# MRF24J40MA_Breakout_verA.net
KiCad netlist of a schematic drawn in EAGLE
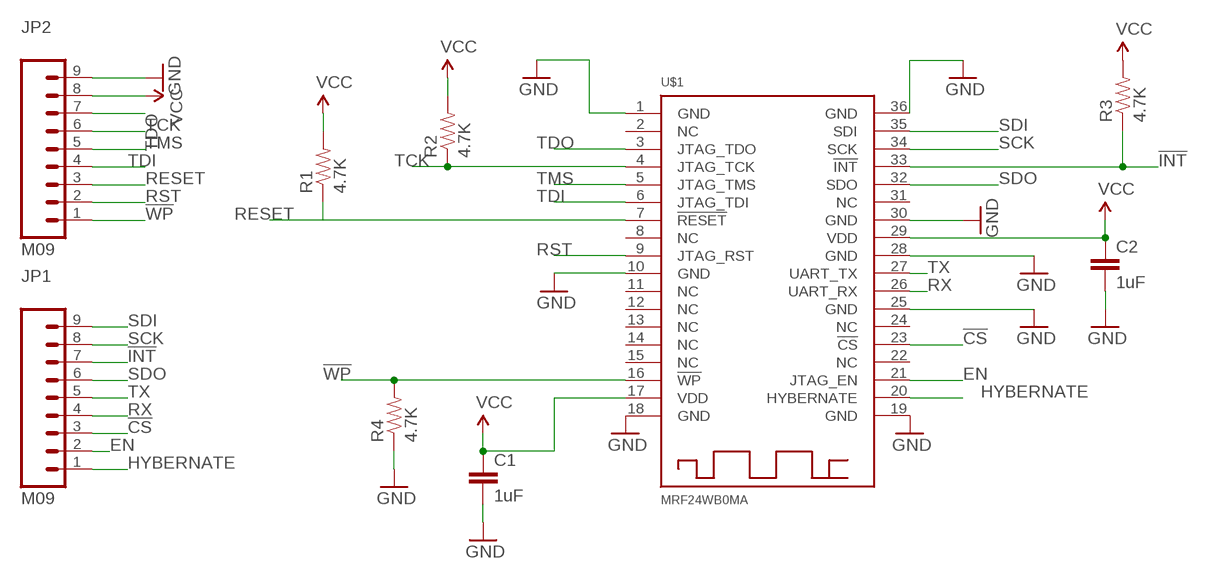
[diagram p0: schematic, sheet 1]

(export (version "E")
  (design (tool "Eeschema 10.0.6"))
  (components
    (comp (ref "C1")
      (value "1uF")
      (footprint "eagle-import:0603-CAP")
      (libsource (lib "eagle-import") (part "CAP0603-CAP"))
    )
    (comp (ref "C2")
      (value "1uF")
      (footprint "eagle-import:0603-CAP")
      (libsource (lib "eagle-import") (part "CAP0603-CAP"))
    )
    (comp (ref "JP1")
      (value "M09")
      (footprint "eagle-import:1X09")
      (libsource (lib "eagle-import") (part "M09"))
    )
    (comp (ref "JP2")
      (value "M09")
      (footprint "eagle-import:1X09")
      (libsource (lib "eagle-import") (part "M09"))
    )
    (comp (ref "R1")
      (value "4.7K")
      (footprint "eagle-import:0603-RES")
      (libsource (lib "eagle-import") (part "RESISTOR0603-RES"))
    )
    (comp (ref "R2")
      (value "4.7K")
      (footprint "eagle-import:0603-RES")
      (libsource (lib "eagle-import") (part "RESISTOR0603-RES"))
    )
    (comp (ref "R3")
      (value "4.7K")
      (footprint "eagle-import:0603-RES")
      (libsource (lib "eagle-import") (part "RESISTOR0603-RES"))
    )
    (comp (ref "R4")
      (value "4.7K")
      (footprint "eagle-import:0603-RES")
      (libsource (lib "eagle-import") (part "RESISTOR0603-RES"))
    )
    (comp (ref "U$1")
      (value "MRF24WB0MA")
      (footprint "eagle-import:MRF24WB0MA")
      (libsource (lib "eagle-import") (part "MRF24WB0MA"))
    )
  )
  (nets
    (net (code "1") (name "/EN") (class "Default")
      (node (ref "JP1") (pin "2") (pinfunction "2_2") (pintype "passive"))
      (node (ref "U$1") (pin "21") (pinfunction "JTAG_EN_21") (pintype "bidirectional"))
    )
    (net (code "2") (name "/HYBERNATE") (class "Default")
      (node (ref "JP1") (pin "1") (pinfunction "1_1") (pintype "passive"))
      (node (ref "U$1") (pin "20") (pinfunction "HYBERNATE_20") (pintype "bidirectional"))
    )
    (net (code "3") (name "/RESET") (class "Default")
      (node (ref "JP2") (pin "3") (pinfunction "3_3") (pintype "passive"))
      (node (ref "R1") (pin "1") (pinfunction "1_1") (pintype "passive"))
      (node (ref "U$1") (pin "7") (pinfunction "~{RESET}_7") (pintype "bidirectional"))
    )
    (net (code "4") (name "/RST") (class "Default")
      (node (ref "JP2") (pin "2") (pinfunction "2_2") (pintype "passive"))
      (node (ref "U$1") (pin "9") (pinfunction "JTAG_RST_9") (pintype "bidirectional"))
    )
    (net (code "5") (name "/RX") (class "Default")
      (node (ref "JP1") (pin "4") (pinfunction "4_4") (pintype "passive"))
      (node (ref "U$1") (pin "26") (pinfunction "UART_RX_26") (pintype "bidirectional"))
    )
    (net (code "6") (name "/SCK") (class "Default")
      (node (ref "JP1") (pin "8") (pinfunction "8_8") (pintype "passive"))
      (node (ref "U$1") (pin "34") (pinfunction "SCK_34") (pintype "bidirectional"))
    )
    (net (code "7") (name "/SDI") (class "Default")
      (node (ref "JP1") (pin "9") (pinfunction "9_9") (pintype "passive"))
      (node (ref "U$1") (pin "35") (pinfunction "SDI_35") (pintype "bidirectional"))
    )
    (net (code "8") (name "/SDO") (class "Default")
      (node (ref "JP1") (pin "6") (pinfunction "6_6") (pintype "passive"))
      (node (ref "U$1") (pin "32") (pinfunction "SDO_32") (pintype "bidirectional"))
    )
    (net (code "9") (name "/TCK") (class "Default")
      (node (ref "JP2") (pin "6") (pinfunction "6_6") (pintype "passive"))
      (node (ref "R2") (pin "1") (pinfunction "1_1") (pintype "passive"))
      (node (ref "U$1") (pin "4") (pinfunction "JTAG_TCK_4") (pintype "bidirectional"))
    )
    (net (code "10") (name "/TDI") (class "Default")
      (node (ref "JP2") (pin "4") (pinfunction "4_4") (pintype "passive"))
      (node (ref "U$1") (pin "6") (pinfunction "JTAG_TDI_6") (pintype "bidirectional"))
    )
    (net (code "11") (name "/TDO") (class "Default")
      (node (ref "JP2") (pin "7") (pinfunction "7_7") (pintype "passive"))
      (node (ref "U$1") (pin "3") (pinfunction "JTAG_TDO_3") (pintype "bidirectional"))
    )
    (net (code "12") (name "/TMS") (class "Default")
      (node (ref "JP2") (pin "5") (pinfunction "5_5") (pintype "passive"))
      (node (ref "U$1") (pin "5") (pinfunction "JTAG_TMS_5") (pintype "bidirectional"))
    )
    (net (code "13") (name "/TX") (class "Default")
      (node (ref "JP1") (pin "5") (pinfunction "5_5") (pintype "passive"))
      (node (ref "U$1") (pin "27") (pinfunction "UART_TX_27") (pintype "bidirectional"))
    )
    (net (code "14") (name "/~{CS}") (class "Default")
      (node (ref "JP1") (pin "3") (pinfunction "3_3") (pintype "passive"))
      (node (ref "U$1") (pin "23") (pinfunction "~{CS}_23") (pintype "bidirectional"))
    )
    (net (code "15") (name "/~{INT}") (class "Default")
      (node (ref "JP1") (pin "7") (pinfunction "7_7") (pintype "passive"))
      (node (ref "R3") (pin "1") (pinfunction "1_1") (pintype "passive"))
      (node (ref "U$1") (pin "33") (pinfunction "~{INT}_33") (pintype "bidirectional"))
    )
    (net (code "16") (name "/~{WP}") (class "Default")
      (node (ref "JP2") (pin "1") (pinfunction "1_1") (pintype "passive"))
      (node (ref "R4") (pin "2") (pinfunction "2_2") (pintype "passive"))
      (node (ref "U$1") (pin "16") (pinfunction "~{WP}_16") (pintype "bidirectional"))
    )
    (net (code "17") (name "GND") (class "Default")
      (node (ref "C1") (pin "2") (pinfunction "2_2") (pintype "passive"))
      (node (ref "C2") (pin "2") (pinfunction "2_2") (pintype "passive"))
      (node (ref "JP2") (pin "9") (pinfunction "9_9") (pintype "passive"))
      (node (ref "R4") (pin "1") (pinfunction "1_1") (pintype "passive"))
      (node (ref "U$1") (pin "1") (pinfunction "GND_1") (pintype "bidirectional"))
      (node (ref "U$1") (pin "10") (pinfunction "GND_10") (pintype "bidirectional"))
      (node (ref "U$1") (pin "18") (pinfunction "GND_18") (pintype "bidirectional"))
      (node (ref "U$1") (pin "19") (pinfunction "GND_19") (pintype "bidirectional"))
      (node (ref "U$1") (pin "25") (pinfunction "GND_25") (pintype "bidirectional"))
      (node (ref "U$1") (pin "28") (pinfunction "GND_28") (pintype "bidirectional"))
      (node (ref "U$1") (pin "30") (pinfunction "GND_30") (pintype "bidirectional"))
      (node (ref "U$1") (pin "36") (pinfunction "GND_36") (pintype "bidirectional"))
    )
    (net (code "18") (name "VCC") (class "Default")
      (node (ref "C1") (pin "1") (pinfunction "1_1") (pintype "passive"))
      (node (ref "C2") (pin "1") (pinfunction "1_1") (pintype "passive"))
      (node (ref "JP2") (pin "8") (pinfunction "8_8") (pintype "passive"))
      (node (ref "R1") (pin "2") (pinfunction "2_2") (pintype "passive"))
      (node (ref "R2") (pin "2") (pinfunction "2_2") (pintype "passive"))
      (node (ref "R3") (pin "2") (pinfunction "2_2") (pintype "passive"))
      (node (ref "U$1") (pin "17") (pinfunction "VDD_17") (pintype "bidirectional"))
      (node (ref "U$1") (pin "29") (pinfunction "VDD_29") (pintype "bidirectional"))
    )
    (net (code "19") (name "unconnected-(U$1-NC-Pad2)") (class "Default")
      (node (ref "U$1") (pin "2") (pinfunction "NC_2") (pintype "bidirectional"))
    )
    (net (code "20") (name "unconnected-(U$1-NC-Pad8)") (class "Default")
      (node (ref "U$1") (pin "8") (pinfunction "NC_8") (pintype "bidirectional"))
    )
    (net (code "21") (name "unconnected-(U$1-NC-Pad11)") (class "Default")
      (node (ref "U$1") (pin "11") (pinfunction "NC_11") (pintype "bidirectional"))
    )
    (net (code "22") (name "unconnected-(U$1-NC-Pad12)") (class "Default")
      (node (ref "U$1") (pin "12") (pinfunction "NC_12") (pintype "bidirectional"))
    )
    (net (code "23") (name "unconnected-(U$1-NC-Pad13)") (class "Default")
      (node (ref "U$1") (pin "13") (pinfunction "NC_13") (pintype "bidirectional"))
    )
    (net (code "24") (name "unconnected-(U$1-NC-Pad14)") (class "Default")
      (node (ref "U$1") (pin "14") (pinfunction "NC_14") (pintype "bidirectional"))
    )
    (net (code "25") (name "unconnected-(U$1-NC-Pad15)") (class "Default")
      (node (ref "U$1") (pin "15") (pinfunction "NC_15") (pintype "bidirectional"))
    )
    (net (code "26") (name "unconnected-(U$1-NC-Pad22)") (class "Default")
      (node (ref "U$1") (pin "22") (pinfunction "NC_22") (pintype "bidirectional"))
    )
    (net (code "27") (name "unconnected-(U$1-NC-Pad24)") (class "Default")
      (node (ref "U$1") (pin "24") (pinfunction "NC_24") (pintype "bidirectional"))
    )
    (net (code "28") (name "unconnected-(U$1-NC-Pad31)") (class "Default")
      (node (ref "U$1") (pin "31") (pinfunction "NC_31") (pintype "bidirectional"))
    )
  )
)
